# Buck-Boost-Switch-Mode-Power-Supply-Modu.net
KiCad netlist of a schematic drawn in EAGLE
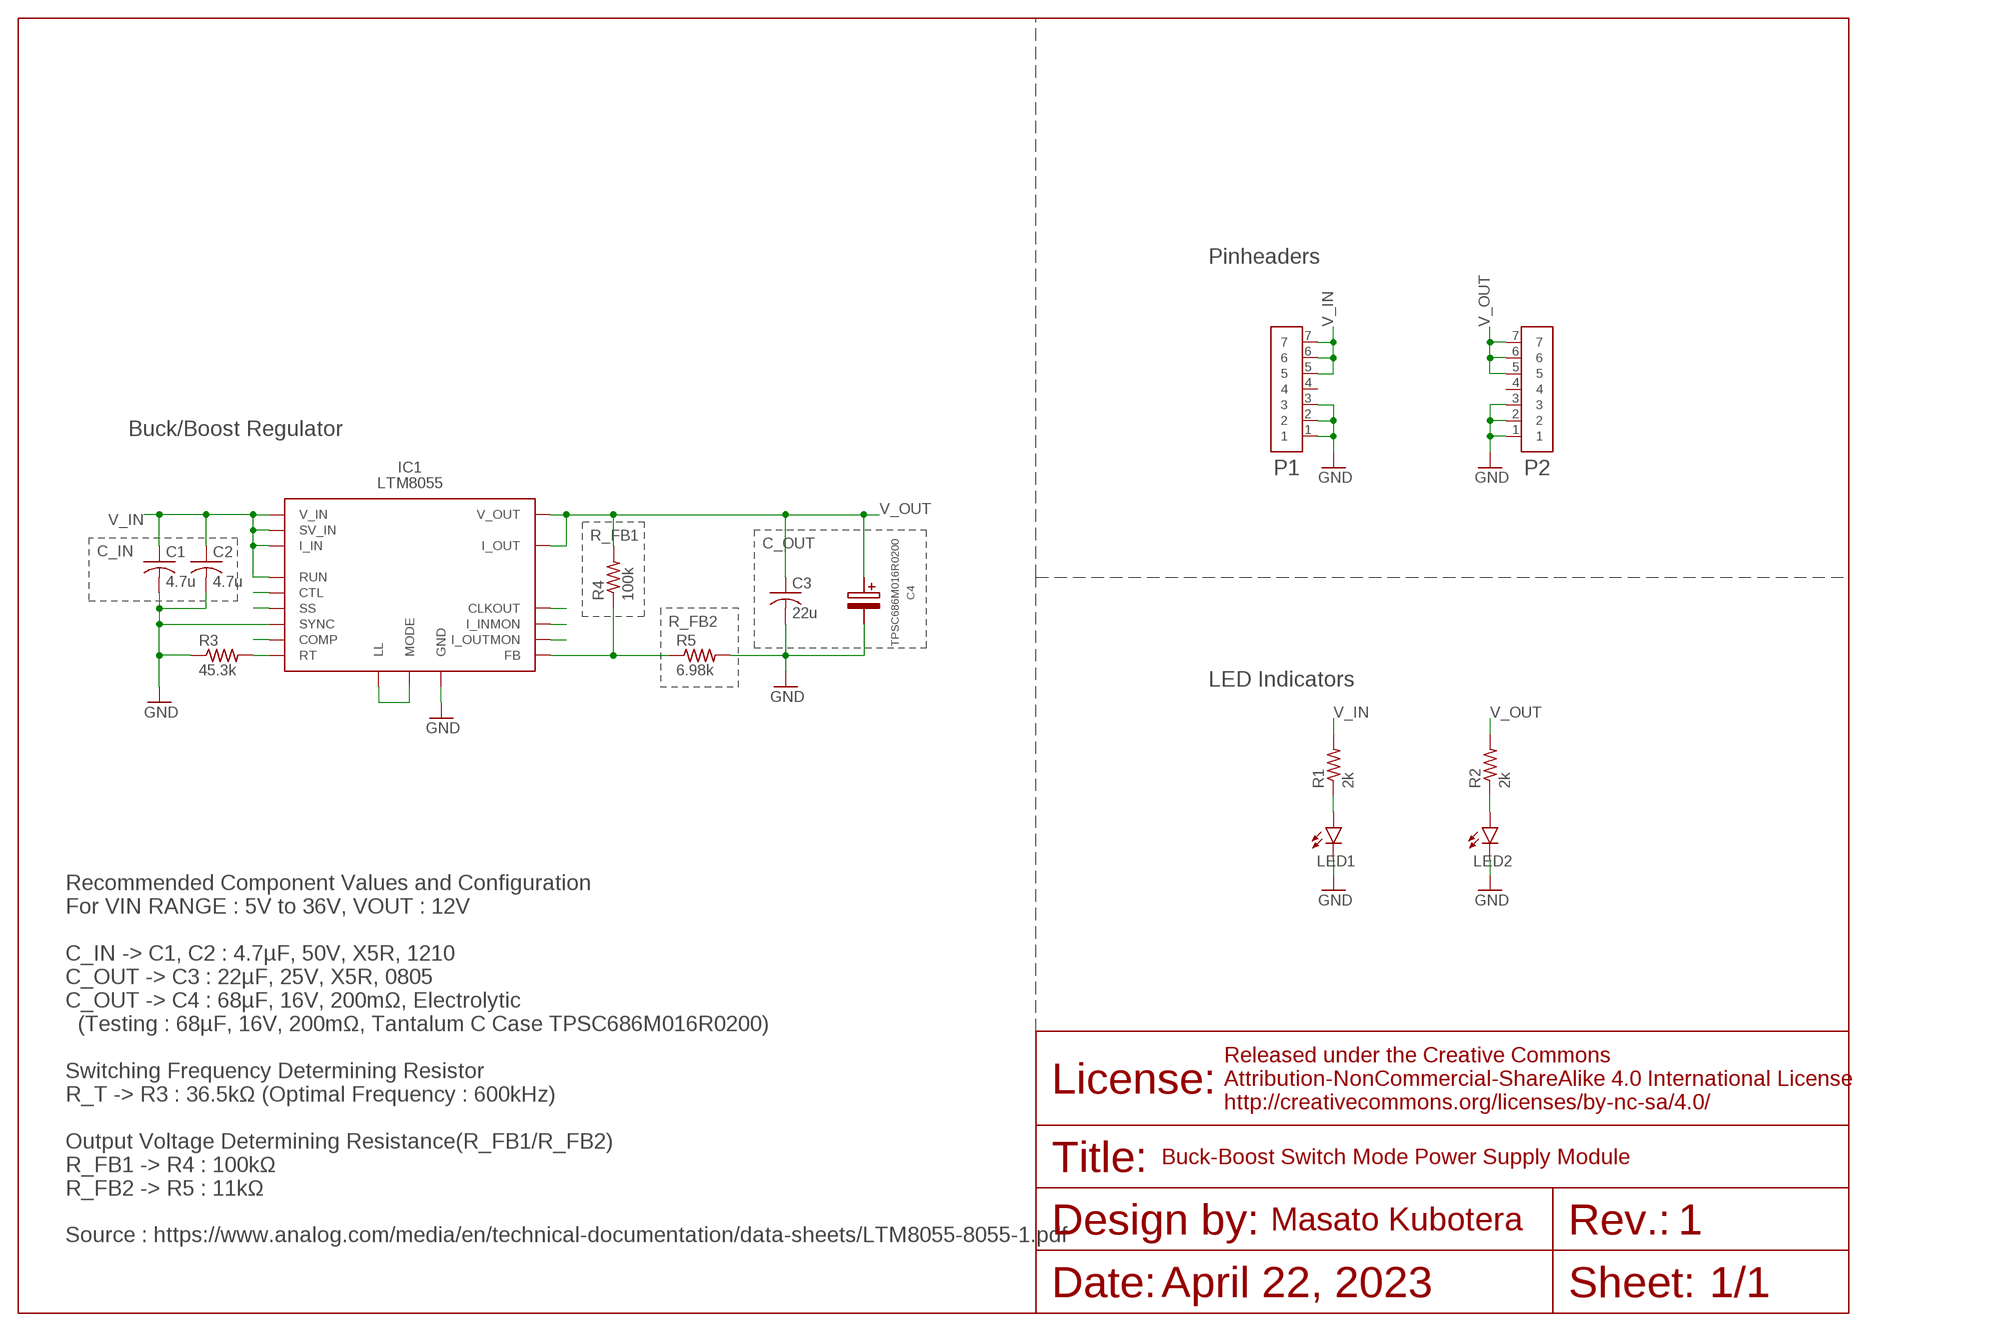
[diagram p0: schematic, sheet 1]

(export (version "E")
  (design (tool "Eeschema 10.0.6"))
  (components
    (comp (ref "C1")
      (value "4.7u")
      (footprint "eagle-import:C0805")
      (libsource (lib "eagle-import") (part "C-USC0805"))
    )
    (comp (ref "C2")
      (value "4.7u")
      (footprint "eagle-import:C0805")
      (libsource (lib "eagle-import") (part "C-USC0805"))
    )
    (comp (ref "C3")
      (value "22u")
      (footprint "eagle-import:C0805")
      (libsource (lib "eagle-import") (part "C-USC0805"))
    )
    (comp (ref "C4")
      (value "TPSC686M016R0200")
      (footprint "eagle-import:TPSC686M016R0200")
      (libsource (lib "eagle-import") (part "TPSC686M016R0200"))
    )
    (comp (ref "IC1")
      (value "LTM8055")
      (footprint "eagle-import:LTM8055")
      (libsource (lib "eagle-import") (part "LTM8055"))
    )
    (comp (ref "LED1")
      (value "LEDSML0603")
      (footprint "eagle-import:SML0603")
      (libsource (lib "eagle-import") (part "LEDSML0603"))
    )
    (comp (ref "LED2")
      (value "LEDSML0603")
      (footprint "eagle-import:SML0603")
      (libsource (lib "eagle-import") (part "LEDSML0603"))
    )
    (comp (ref "P1")
      (value "PINHEADER-7P")
      (footprint "eagle-import:7P")
      (libsource (lib "eagle-import") (part "PINHEADER-7P"))
    )
    (comp (ref "P2")
      (value "PINHEADER-7P")
      (footprint "eagle-import:7P")
      (libsource (lib "eagle-import") (part "PINHEADER-7P"))
    )
    (comp (ref "R1")
      (value "2k")
      (footprint "eagle-import:R0603")
      (libsource (lib "eagle-import") (part "R-US_R0603"))
    )
    (comp (ref "R2")
      (value "2k")
      (footprint "eagle-import:R0603")
      (libsource (lib "eagle-import") (part "R-US_R0603"))
    )
    (comp (ref "R3")
      (value "45.3k")
      (footprint "eagle-import:R0603")
      (libsource (lib "eagle-import") (part "R-US_R0603"))
    )
    (comp (ref "R4")
      (value "100k")
      (footprint "eagle-import:R0603")
      (libsource (lib "eagle-import") (part "R-US_R0603"))
    )
    (comp (ref "R5")
      (value "6.98k")
      (footprint "eagle-import:R0603")
      (libsource (lib "eagle-import") (part "R-US_R0603"))
    )
  )
  (nets
    (net (code "1") (name "/V_IN") (class "Default")
      (node (ref "C1") (pin "1") (pinfunction "1_1") (pintype "passive"))
      (node (ref "C2") (pin "1") (pinfunction "1_1") (pintype "passive"))
      (node (ref "IC1") (pin "F10") (pinfunction "SV_IN_F10") (pintype "bidirectional"))
      (node (ref "IC1") (pin "F11") (pinfunction "SV_IN_F11") (pintype "bidirectional"))
      (node (ref "IC1") (pin "G10") (pinfunction "V_IN_G10") (pintype "bidirectional"))
      (node (ref "IC1") (pin "G11") (pinfunction "V_IN_G11") (pintype "bidirectional"))
      (node (ref "IC1") (pin "H10") (pinfunction "V_IN_H10") (pintype "bidirectional"))
      (node (ref "IC1") (pin "H11") (pinfunction "V_IN_H11") (pintype "bidirectional"))
      (node (ref "IC1") (pin "J10") (pinfunction "V_IN_J10") (pintype "bidirectional"))
      (node (ref "IC1") (pin "J11") (pinfunction "V_IN_J11") (pintype "bidirectional"))
      (node (ref "IC1") (pin "K10") (pinfunction "V_IN_K10") (pintype "bidirectional"))
      (node (ref "IC1") (pin "K11") (pinfunction "V_IN_K11") (pintype "bidirectional"))
      (node (ref "IC1") (pin "L10") (pinfunction "V_IN_L10") (pintype "bidirectional"))
      (node (ref "IC1") (pin "L11") (pinfunction "V_IN_L11") (pintype "bidirectional"))
      (node (ref "IC1") (pin "L4") (pinfunction "RUN_L4") (pintype "bidirectional"))
      (node (ref "IC1") (pin "L9") (pinfunction "I_IN_L9") (pintype "bidirectional"))
      (node (ref "P1") (pin "5") (pinfunction "5_5") (pintype "bidirectional"))
      (node (ref "P1") (pin "6") (pinfunction "6_6") (pintype "bidirectional"))
      (node (ref "P1") (pin "7") (pinfunction "7_7") (pintype "bidirectional"))
      (node (ref "R1") (pin "2") (pinfunction "2_2") (pintype "passive"))
    )
    (net (code "2") (name "/V_OUT") (class "Default")
      (node (ref "C3") (pin "1") (pinfunction "1_1") (pintype "passive"))
      (node (ref "C4") (pin "+") (pinfunction "+_+") (pintype "bidirectional"))
      (node (ref "IC1") (pin "A1") (pinfunction "V_OUT_A1") (pintype "bidirectional"))
      (node (ref "IC1") (pin "A2") (pinfunction "V_OUT_A2") (pintype "bidirectional"))
      (node (ref "IC1") (pin "A3") (pinfunction "V_OUT_A3") (pintype "bidirectional"))
      (node (ref "IC1") (pin "A4") (pinfunction "V_OUT_A4") (pintype "bidirectional"))
      (node (ref "IC1") (pin "A5") (pinfunction "V_OUT_A5") (pintype "bidirectional"))
      (node (ref "IC1") (pin "A6") (pinfunction "V_OUT_A6") (pintype "bidirectional"))
      (node (ref "IC1") (pin "B1") (pinfunction "V_OUT_B1") (pintype "bidirectional"))
      (node (ref "IC1") (pin "B2") (pinfunction "V_OUT_B2") (pintype "bidirectional"))
      (node (ref "IC1") (pin "B3") (pinfunction "V_OUT_B3") (pintype "bidirectional"))
      (node (ref "IC1") (pin "B4") (pinfunction "V_OUT_B4") (pintype "bidirectional"))
      (node (ref "IC1") (pin "B5") (pinfunction "V_OUT_B5") (pintype "bidirectional"))
      (node (ref "IC1") (pin "B6") (pinfunction "V_OUT_B6") (pintype "bidirectional"))
      (node (ref "IC1") (pin "C1") (pinfunction "V_OUT_C1") (pintype "bidirectional"))
      (node (ref "IC1") (pin "C2") (pinfunction "V_OUT_C2") (pintype "bidirectional"))
      (node (ref "IC1") (pin "C3") (pinfunction "V_OUT_C3") (pintype "bidirectional"))
      (node (ref "IC1") (pin "C4") (pinfunction "V_OUT_C4") (pintype "bidirectional"))
      (node (ref "IC1") (pin "C5") (pinfunction "V_OUT_C5") (pintype "bidirectional"))
      (node (ref "IC1") (pin "C6") (pinfunction "V_OUT_C6") (pintype "bidirectional"))
      (node (ref "IC1") (pin "D1") (pinfunction "I_OUT_D1") (pintype "bidirectional"))
      (node (ref "P2") (pin "5") (pinfunction "5_5") (pintype "bidirectional"))
      (node (ref "P2") (pin "6") (pinfunction "6_6") (pintype "bidirectional"))
      (node (ref "P2") (pin "7") (pinfunction "7_7") (pintype "bidirectional"))
      (node (ref "R2") (pin "2") (pinfunction "2_2") (pintype "passive"))
      (node (ref "R4") (pin "2") (pinfunction "2_2") (pintype "passive"))
    )
    (net (code "3") (name "GND") (class "Default")
      (node (ref "C1") (pin "2") (pinfunction "2_2") (pintype "passive"))
      (node (ref "C2") (pin "2") (pinfunction "2_2") (pintype "passive"))
      (node (ref "C3") (pin "2") (pinfunction "2_2") (pintype "passive"))
      (node (ref "C4") (pin "-") (pinfunction "-_-") (pintype "bidirectional"))
      (node (ref "IC1") (pin "A10") (pinfunction "GND_A10") (pintype "bidirectional"))
      (node (ref "IC1") (pin "A11") (pinfunction "GND_A11") (pintype "bidirectional"))
      (node (ref "IC1") (pin "A7") (pinfunction "GND_A7") (pintype "bidirectional"))
      (node (ref "IC1") (pin "A8") (pinfunction "GND_A8") (pintype "bidirectional"))
      (node (ref "IC1") (pin "A9") (pinfunction "GND_A9") (pintype "bidirectional"))
      (node (ref "IC1") (pin "B10") (pinfunction "GND_B10") (pintype "bidirectional"))
      (node (ref "IC1") (pin "B11") (pinfunction "GND_B11") (pintype "bidirectional"))
      (node (ref "IC1") (pin "B7") (pinfunction "GND_B7") (pintype "bidirectional"))
      (node (ref "IC1") (pin "B8") (pinfunction "GND_B8") (pintype "bidirectional"))
      (node (ref "IC1") (pin "B9") (pinfunction "GND_B9") (pintype "bidirectional"))
      (node (ref "IC1") (pin "C10") (pinfunction "GND_C10") (pintype "bidirectional"))
      (node (ref "IC1") (pin "C11") (pinfunction "GND_C11") (pintype "bidirectional"))
      (node (ref "IC1") (pin "C7") (pinfunction "GND_C7") (pintype "bidirectional"))
      (node (ref "IC1") (pin "C8") (pinfunction "GND_C8") (pintype "bidirectional"))
      (node (ref "IC1") (pin "C9") (pinfunction "GND_C9") (pintype "bidirectional"))
      (node (ref "IC1") (pin "D10") (pinfunction "GND_D10") (pintype "bidirectional"))
      (node (ref "IC1") (pin "D11") (pinfunction "GND_D11") (pintype "bidirectional"))
      (node (ref "IC1") (pin "D2") (pinfunction "GND_D2") (pintype "bidirectional"))
      (node (ref "IC1") (pin "D3") (pinfunction "GND_D3") (pintype "bidirectional"))
      (node (ref "IC1") (pin "D4") (pinfunction "GND_D4") (pintype "bidirectional"))
      (node (ref "IC1") (pin "D5") (pinfunction "GND_D5") (pintype "bidirectional"))
      (node (ref "IC1") (pin "D6") (pinfunction "GND_D6") (pintype "bidirectional"))
      (node (ref "IC1") (pin "D7") (pinfunction "GND_D7") (pintype "bidirectional"))
      (node (ref "IC1") (pin "D8") (pinfunction "GND_D8") (pintype "bidirectional"))
      (node (ref "IC1") (pin "D9") (pinfunction "GND_D9") (pintype "bidirectional"))
      (node (ref "IC1") (pin "E1") (pinfunction "GND_E1") (pintype "bidirectional"))
      (node (ref "IC1") (pin "E10") (pinfunction "GND_E10") (pintype "bidirectional"))
      (node (ref "IC1") (pin "E11") (pinfunction "GND_E11") (pintype "bidirectional"))
      (node (ref "IC1") (pin "E2") (pinfunction "GND_E2") (pintype "bidirectional"))
      (node (ref "IC1") (pin "E3") (pinfunction "GND_E3") (pintype "bidirectional"))
      (node (ref "IC1") (pin "E4") (pinfunction "GND_E4") (pintype "bidirectional"))
      (node (ref "IC1") (pin "E5") (pinfunction "GND_E5") (pintype "bidirectional"))
      (node (ref "IC1") (pin "E6") (pinfunction "GND_E6") (pintype "bidirectional"))
      (node (ref "IC1") (pin "E7") (pinfunction "GND_E7") (pintype "bidirectional"))
      (node (ref "IC1") (pin "E8") (pinfunction "GND_E8") (pintype "bidirectional"))
      (node (ref "IC1") (pin "E9") (pinfunction "GND_E9") (pintype "bidirectional"))
      (node (ref "IC1") (pin "F2") (pinfunction "GND_F2") (pintype "bidirectional"))
      (node (ref "IC1") (pin "F3") (pinfunction "GND_F3") (pintype "bidirectional"))
      (node (ref "IC1") (pin "F4") (pinfunction "GND_F4") (pintype "bidirectional"))
      (node (ref "IC1") (pin "F5") (pinfunction "GND_F5") (pintype "bidirectional"))
      (node (ref "IC1") (pin "F6") (pinfunction "GND_F6") (pintype "bidirectional"))
      (node (ref "IC1") (pin "F7") (pinfunction "GND_F7") (pintype "bidirectional"))
      (node (ref "IC1") (pin "F8") (pinfunction "GND_F8") (pintype "bidirectional"))
      (node (ref "IC1") (pin "F9") (pinfunction "GND_F9") (pintype "bidirectional"))
      (node (ref "IC1") (pin "G3") (pinfunction "GND_G3") (pintype "bidirectional"))
      (node (ref "IC1") (pin "G4") (pinfunction "GND_G4") (pintype "bidirectional"))
      (node (ref "IC1") (pin "G5") (pinfunction "GND_G5") (pintype "bidirectional"))
      (node (ref "IC1") (pin "G6") (pinfunction "GND_G6") (pintype "bidirectional"))
      (node (ref "IC1") (pin "G7") (pinfunction "GND_G7") (pintype "bidirectional"))
      (node (ref "IC1") (pin "G8") (pinfunction "GND_G8") (pintype "bidirectional"))
      (node (ref "IC1") (pin "G9") (pinfunction "GND_G9") (pintype "bidirectional"))
      (node (ref "IC1") (pin "H2") (pinfunction "SYNC_H2") (pintype "bidirectional"))
      (node (ref "IC1") (pin "H3") (pinfunction "GND_H3") (pintype "bidirectional"))
      (node (ref "IC1") (pin "H4") (pinfunction "GND_H4") (pintype "bidirectional"))
      (node (ref "IC1") (pin "H5") (pinfunction "GND_H5") (pintype "bidirectional"))
      (node (ref "IC1") (pin "H6") (pinfunction "GND_H6") (pintype "bidirectional"))
      (node (ref "IC1") (pin "H7") (pinfunction "GND_H7") (pintype "bidirectional"))
      (node (ref "IC1") (pin "H8") (pinfunction "GND_H8") (pintype "bidirectional"))
      (node (ref "IC1") (pin "H9") (pinfunction "GND_H9") (pintype "bidirectional"))
      (node (ref "IC1") (pin "J3") (pinfunction "GND_J3") (pintype "bidirectional"))
      (node (ref "IC1") (pin "J4") (pinfunction "GND_J4") (pintype "bidirectional"))
      (node (ref "IC1") (pin "J5") (pinfunction "GND_J5") (pintype "bidirectional"))
      (node (ref "IC1") (pin "J6") (pinfunction "GND_J6") (pintype "bidirectional"))
      (node (ref "IC1") (pin "J7") (pinfunction "GND_J7") (pintype "bidirectional"))
      (node (ref "IC1") (pin "J8") (pinfunction "GND_J8") (pintype "bidirectional"))
      (node (ref "IC1") (pin "J9") (pinfunction "GND_J9") (pintype "bidirectional"))
      (node (ref "IC1") (pin "K3") (pinfunction "GND_K3") (pintype "bidirectional"))
      (node (ref "IC1") (pin "K4") (pinfunction "GND_K4") (pintype "bidirectional"))
      (node (ref "IC1") (pin "K5") (pinfunction "GND_K5") (pintype "bidirectional"))
      (node (ref "IC1") (pin "K6") (pinfunction "GND_K6") (pintype "bidirectional"))
      (node (ref "IC1") (pin "K7") (pinfunction "GND_K7") (pintype "bidirectional"))
      (node (ref "IC1") (pin "K8") (pinfunction "GND_K8") (pintype "bidirectional"))
      (node (ref "IC1") (pin "K9") (pinfunction "GND_K9") (pintype "bidirectional"))
      (node (ref "IC1") (pin "L1") (pinfunction "GND_L1") (pintype "bidirectional"))
      (node (ref "IC1") (pin "L5") (pinfunction "GND_L5") (pintype "bidirectional"))
      (node (ref "IC1") (pin "L6") (pinfunction "GND_L6") (pintype "bidirectional"))
      (node (ref "IC1") (pin "L7") (pinfunction "GND_L7") (pintype "bidirectional"))
      (node (ref "IC1") (pin "L8") (pinfunction "GND_L8") (pintype "bidirectional"))
      (node (ref "LED1") (pin "C") (pinfunction "C_C") (pintype "passive"))
      (node (ref "LED2") (pin "C") (pinfunction "C_C") (pintype "passive"))
      (node (ref "P1") (pin "1") (pinfunction "1_1") (pintype "bidirectional"))
      (node (ref "P1") (pin "2") (pinfunction "2_2") (pintype "bidirectional"))
      (node (ref "P1") (pin "3") (pinfunction "3_3") (pintype "bidirectional"))
      (node (ref "P2") (pin "1") (pinfunction "1_1") (pintype "bidirectional"))
      (node (ref "P2") (pin "2") (pinfunction "2_2") (pintype "bidirectional"))
      (node (ref "P2") (pin "3") (pinfunction "3_3") (pintype "bidirectional"))
      (node (ref "R3") (pin "1") (pinfunction "1_1") (pintype "passive"))
      (node (ref "R5") (pin "2") (pinfunction "2_2") (pintype "passive"))
    )
    (net (code "4") (name "Net-(IC1-FB)") (class "Default")
      (node (ref "IC1") (pin "J1") (pinfunction "FB_J1") (pintype "bidirectional"))
      (node (ref "R4") (pin "1") (pinfunction "1_1") (pintype "passive"))
      (node (ref "R5") (pin "1") (pinfunction "1_1") (pintype "passive"))
    )
    (net (code "5") (name "Net-(IC1-LL)") (class "Default")
      (node (ref "IC1") (pin "F1") (pinfunction "LL_F1") (pintype "bidirectional"))
      (node (ref "IC1") (pin "G2") (pinfunction "MODE_G2") (pintype "bidirectional"))
    )
    (net (code "6") (name "Net-(IC1-RT)") (class "Default")
      (node (ref "IC1") (pin "H1") (pinfunction "RT_H1") (pintype "bidirectional"))
      (node (ref "R3") (pin "2") (pinfunction "2_2") (pintype "passive"))
    )
    (net (code "7") (name "Net-(LED1-PadA)") (class "Default")
      (node (ref "LED1") (pin "A") (pinfunction "A_A") (pintype "passive"))
      (node (ref "R1") (pin "1") (pinfunction "1_1") (pintype "passive"))
    )
    (net (code "8") (name "Net-(LED2-PadA)") (class "Default")
      (node (ref "LED2") (pin "A") (pinfunction "A_A") (pintype "passive"))
      (node (ref "R2") (pin "1") (pinfunction "1_1") (pintype "passive"))
    )
    (net (code "9") (name "unconnected-(IC1-CLKOUT-PadG1)") (class "Default")
      (node (ref "IC1") (pin "G1") (pinfunction "CLKOUT_G1") (pintype "bidirectional"))
    )
    (net (code "10") (name "unconnected-(IC1-COMP-PadJ2)") (class "Default")
      (node (ref "IC1") (pin "J2") (pinfunction "COMP_J2") (pintype "bidirectional"))
    )
    (net (code "11") (name "unconnected-(IC1-CTL-PadK2)") (class "Default")
      (node (ref "IC1") (pin "K2") (pinfunction "CTL_K2") (pintype "bidirectional"))
    )
    (net (code "12") (name "unconnected-(IC1-I_INMON-PadL3)") (class "Default")
      (node (ref "IC1") (pin "L3") (pinfunction "I_INMON_L3") (pintype "bidirectional"))
    )
    (net (code "13") (name "unconnected-(IC1-I_OUTMON-PadL2)") (class "Default")
      (node (ref "IC1") (pin "L2") (pinfunction "I_OUTMON_L2") (pintype "bidirectional"))
    )
    (net (code "14") (name "unconnected-(IC1-SS-PadK1)") (class "Default")
      (node (ref "IC1") (pin "K1") (pinfunction "SS_K1") (pintype "bidirectional"))
    )
    (net (code "15") (name "unconnected-(P1-Pad4)") (class "Default")
      (node (ref "P1") (pin "4") (pinfunction "4_4") (pintype "bidirectional"))
    )
    (net (code "16") (name "unconnected-(P2-Pad4)") (class "Default")
      (node (ref "P2") (pin "4") (pinfunction "4_4") (pintype "bidirectional"))
    )
  )
)
